# LCD.net
KiCad netlist of a schematic drawn in Altium Designer
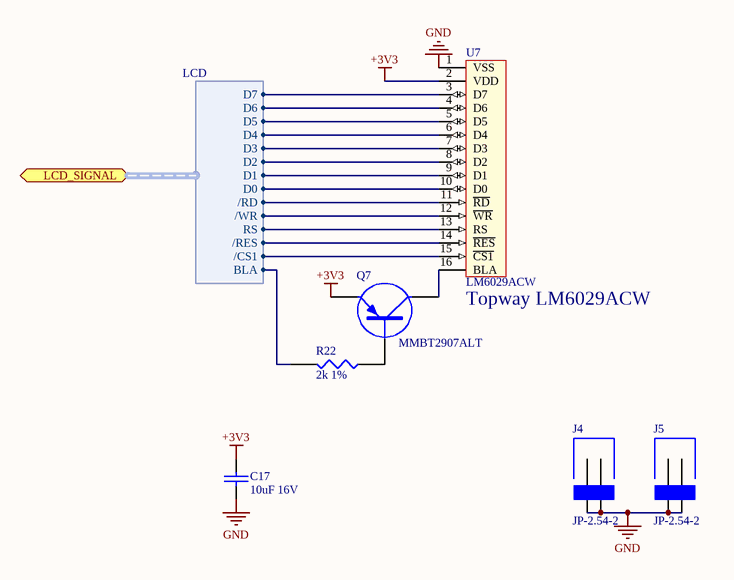
[diagram p0: LCD.SchDoc]

(export (version "E")
  (design (tool "Eeschema 10.0.6"))
  (components
    (comp (ref "C17")
      (value "10uF 16V")
      (footprint "Chip_Capacitor_N:CAPC3216N")
      (description "Capacitor")
      (libsource (lib "*") (part "CAP"))
    )
    (comp (ref "J4")
      (value "JP-2.54-2")
      (footprint "UserPcbLib:JP2-P2.54")
      (libsource (lib "UserSchlib") (part "JP2-2.54"))
    )
    (comp (ref "J5")
      (value "JP-2.54-2")
      (footprint "UserPcbLib:JP2-P2.54")
      (libsource (lib "UserSchlib") (part "JP2-2.54"))
    )
    (comp (ref "Q7")
      (value "MMBT2907ALT")
      (footprint "SOT23_M:SOT23-3M")
      (description "PNP transitor")
      (libsource (lib "*") (part "MMBT3906"))
    )
    (comp (ref "R22")
      (value "2k 1%")
      (footprint "Chip_Resistor_N:RESC2012N")
      (libsource (lib "*") (part "RES1"))
    )
    (comp (ref "U7")
      (value "LM6029ACW")
      (footprint "UserPcbLib:LM6029A")
      (description "Topway LCD module 3.3V")
      (libsource (lib "UserSchlib") (part "LM6029A"))
    )
  )
  (nets
    (net (code "2") (name "+3V3") (class "Default")
      (node (ref "C17") (pin "1") (pinfunction "1_1") (pintype "passive"))
      (node (ref "Q7") (pin "2") (pinfunction "E_2") (pintype "passive"))
      (node (ref "U7") (pin "2") (pinfunction "VDD_2") (pintype "power_in"))
    )
    (net (code "4") (name "GND") (class "Default")
      (node (ref "C17") (pin "2") (pinfunction "2_2") (pintype "passive"))
      (node (ref "J4") (pin "1") (pinfunction "1_1") (pintype "power_in"))
      (node (ref "J4") (pin "2") (pinfunction "2_2") (pintype "power_in"))
      (node (ref "J5") (pin "1") (pinfunction "1_1") (pintype "power_in"))
      (node (ref "J5") (pin "2") (pinfunction "2_2") (pintype "power_in"))
      (node (ref "U7") (pin "1") (pinfunction "VSS_1") (pintype "power_in"))
    )
    (net (code "5") (name "Net-(Q7-B)") (class "Default")
      (node (ref "Q7") (pin "1") (pinfunction "B_1") (pintype "passive"))
      (node (ref "R22") (pin "1") (pinfunction "1_1") (pintype "passive"))
    )
    (net (code "6") (name "Net-(Q7-C)") (class "Default")
      (node (ref "Q7") (pin "3") (pinfunction "C_3") (pintype "passive"))
      (node (ref "U7") (pin "16") (pinfunction "BLA_16") (pintype "power_in"))
    )
    (net (code "7") (name "unconnected-(R22-Pad2)") (class "Default")
      (node (ref "R22") (pin "2") (pinfunction "2_2") (pintype "passive"))
    )
    (net (code "8") (name "unconnected-(U7-CS1-Pad15)") (class "Default")
      (node (ref "U7") (pin "15") (pinfunction "CS1_15") (pintype "input"))
    )
    (net (code "9") (name "unconnected-(U7-D0-Pad10)") (class "Default")
      (node (ref "U7") (pin "10") (pinfunction "D0_10") (pintype "bidirectional"))
    )
    (net (code "10") (name "unconnected-(U7-D1-Pad9)") (class "Default")
      (node (ref "U7") (pin "9") (pinfunction "D1_9") (pintype "bidirectional"))
    )
    (net (code "11") (name "unconnected-(U7-D2-Pad8)") (class "Default")
      (node (ref "U7") (pin "8") (pinfunction "D2_8") (pintype "bidirectional"))
    )
    (net (code "12") (name "unconnected-(U7-D3-Pad7)") (class "Default")
      (node (ref "U7") (pin "7") (pinfunction "D3_7") (pintype "bidirectional"))
    )
    (net (code "13") (name "unconnected-(U7-D4-Pad6)") (class "Default")
      (node (ref "U7") (pin "6") (pinfunction "D4_6") (pintype "bidirectional"))
    )
    (net (code "14") (name "unconnected-(U7-D5-Pad5)") (class "Default")
      (node (ref "U7") (pin "5") (pinfunction "D5_5") (pintype "bidirectional"))
    )
    (net (code "15") (name "unconnected-(U7-D6-Pad4)") (class "Default")
      (node (ref "U7") (pin "4") (pinfunction "D6_4") (pintype "bidirectional"))
    )
    (net (code "16") (name "unconnected-(U7-D7-Pad3)") (class "Default")
      (node (ref "U7") (pin "3") (pinfunction "D7_3") (pintype "bidirectional"))
    )
    (net (code "17") (name "unconnected-(U7-RD-Pad11)") (class "Default")
      (node (ref "U7") (pin "11") (pinfunction "RD_11") (pintype "input"))
    )
    (net (code "18") (name "unconnected-(U7-RES-Pad14)") (class "Default")
      (node (ref "U7") (pin "14") (pinfunction "RES_14") (pintype "input"))
    )
    (net (code "19") (name "unconnected-(U7-RS-Pad13)") (class "Default")
      (node (ref "U7") (pin "13") (pinfunction "RS_13") (pintype "input"))
    )
    (net (code "20") (name "unconnected-(U7-WR-Pad12)") (class "Default")
      (node (ref "U7") (pin "12") (pinfunction "WR_12") (pintype "input"))
    )
  )
)
